# Dual_powerSupply_ckt_diagram.net
KiCad netlist of a schematic drawn in EAGLE
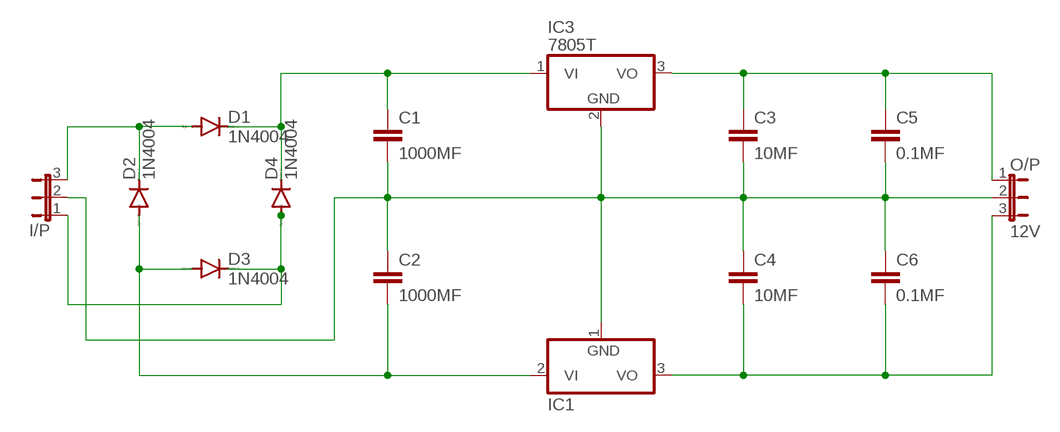
[diagram p0: schematic, sheet 1]

(export (version "E")
  (design (tool "Eeschema 10.0.6"))
  (components
    (comp (ref "C1")
      (value "1000MF")
      (footprint "eagle-import:C2.5-3")
      (libsource (lib "eagle-import") (part "C2,5-3"))
    )
    (comp (ref "C2")
      (value "1000MF")
      (footprint "eagle-import:C2.5-3")
      (libsource (lib "eagle-import") (part "C2,5-3"))
    )
    (comp (ref "C3")
      (value "10MF")
      (footprint "eagle-import:C2.5-3")
      (libsource (lib "eagle-import") (part "C2,5-3"))
    )
    (comp (ref "C4")
      (value "10MF")
      (footprint "eagle-import:C2.5-3")
      (libsource (lib "eagle-import") (part "C2,5-3"))
    )
    (comp (ref "C5")
      (value "0.1MF")
      (footprint "eagle-import:C2.5-3")
      (libsource (lib "eagle-import") (part "C2,5-3"))
    )
    (comp (ref "C6")
      (value "0.1MF")
      (footprint "eagle-import:C2.5-3")
      (libsource (lib "eagle-import") (part "C2,5-3"))
    )
    (comp (ref "D1")
      (value "1N4004")
      (footprint "eagle-import:DO41-10")
      (libsource (lib "eagle-import") (part "1N4004"))
    )
    (comp (ref "D2")
      (value "1N4004")
      (footprint "eagle-import:DO41-10")
      (libsource (lib "eagle-import") (part "1N4004"))
    )
    (comp (ref "D3")
      (value "1N4004")
      (footprint "eagle-import:DO41-10")
      (libsource (lib "eagle-import") (part "1N4004"))
    )
    (comp (ref "D4")
      (value "1N4004")
      (footprint "eagle-import:DO41-10")
      (libsource (lib "eagle-import") (part "1N4004"))
    )
    (comp (ref "I/P")
      (value "JP2E")
      (footprint "eagle-import:JP2")
      (libsource (lib "eagle-import") (part "JP2E"))
    )
    (comp (ref "IC1")
      (value "7905T")
      (footprint "eagle-import:TO220H")
      (libsource (lib "eagle-import") (part "79T05"))
    )
    (comp (ref "IC3")
      (value "7805T")
      (footprint "eagle-import:TO220H")
      (libsource (lib "eagle-import") (part "78T05"))
    )
    (comp (ref "O/P")
      (value "12V")
      (footprint "eagle-import:JP2")
      (libsource (lib "eagle-import") (part "JP2E"))
    )
  )
  (nets
    (net (code "1") (name "Net-(D1-PadA)") (class "Default")
      (node (ref "D1") (pin "A") (pinfunction "A_A") (pintype "passive"))
      (node (ref "D2") (pin "C") (pinfunction "C_C") (pintype "passive"))
      (node (ref "I/P") (pin "3") (pinfunction "3_3") (pintype "passive"))
    )
    (net (code "2") (name "Net-(D3-PadC)") (class "Default")
      (node (ref "D3") (pin "C") (pinfunction "C_C") (pintype "passive"))
      (node (ref "D4") (pin "A") (pinfunction "A_A") (pintype "passive"))
      (node (ref "I/P") (pin "1") (pinfunction "1_1") (pintype "passive"))
    )
    (net (code "3") (name "Net-(IC1-GND)") (class "Default")
      (node (ref "C1") (pin "2") (pinfunction "2_2") (pintype "passive"))
      (node (ref "C2") (pin "1") (pinfunction "1_1") (pintype "passive"))
      (node (ref "C3") (pin "2") (pinfunction "2_2") (pintype "passive"))
      (node (ref "C4") (pin "1") (pinfunction "1_1") (pintype "passive"))
      (node (ref "C5") (pin "2") (pinfunction "2_2") (pintype "passive"))
      (node (ref "C6") (pin "1") (pinfunction "1_1") (pintype "passive"))
      (node (ref "I/P") (pin "2") (pinfunction "2_2") (pintype "passive"))
      (node (ref "IC1") (pin "1") (pinfunction "GND_1") (pintype "passive"))
      (node (ref "IC3") (pin "2") (pinfunction "GND_2") (pintype "passive"))
      (node (ref "O/P") (pin "2") (pinfunction "2_2") (pintype "passive"))
    )
    (net (code "4") (name "Net-(IC1-VI)") (class "Default")
      (node (ref "C2") (pin "2") (pinfunction "2_2") (pintype "passive"))
      (node (ref "D2") (pin "A") (pinfunction "A_A") (pintype "passive"))
      (node (ref "D3") (pin "A") (pinfunction "A_A") (pintype "passive"))
      (node (ref "IC1") (pin "2") (pinfunction "VI_2") (pintype "input"))
    )
    (net (code "5") (name "Net-(IC1-VO)") (class "Default")
      (node (ref "C4") (pin "2") (pinfunction "2_2") (pintype "passive"))
      (node (ref "C6") (pin "2") (pinfunction "2_2") (pintype "passive"))
      (node (ref "IC1") (pin "3") (pinfunction "VO_3") (pintype "passive"))
      (node (ref "O/P") (pin "3") (pinfunction "3_3") (pintype "passive"))
    )
    (net (code "6") (name "Net-(IC3-VI)") (class "Default")
      (node (ref "C1") (pin "1") (pinfunction "1_1") (pintype "passive"))
      (node (ref "D1") (pin "C") (pinfunction "C_C") (pintype "passive"))
      (node (ref "D4") (pin "C") (pinfunction "C_C") (pintype "passive"))
      (node (ref "IC3") (pin "1") (pinfunction "VI_1") (pintype "input"))
    )
    (net (code "7") (name "Net-(IC3-VO)") (class "Default")
      (node (ref "C3") (pin "1") (pinfunction "1_1") (pintype "passive"))
      (node (ref "C5") (pin "1") (pinfunction "1_1") (pintype "passive"))
      (node (ref "IC3") (pin "3") (pinfunction "VO_3") (pintype "passive"))
      (node (ref "O/P") (pin "1") (pinfunction "1_1") (pintype "passive"))
    )
  )
)
